# mattduino_v7.net
KiCad netlist of a schematic drawn in EAGLE
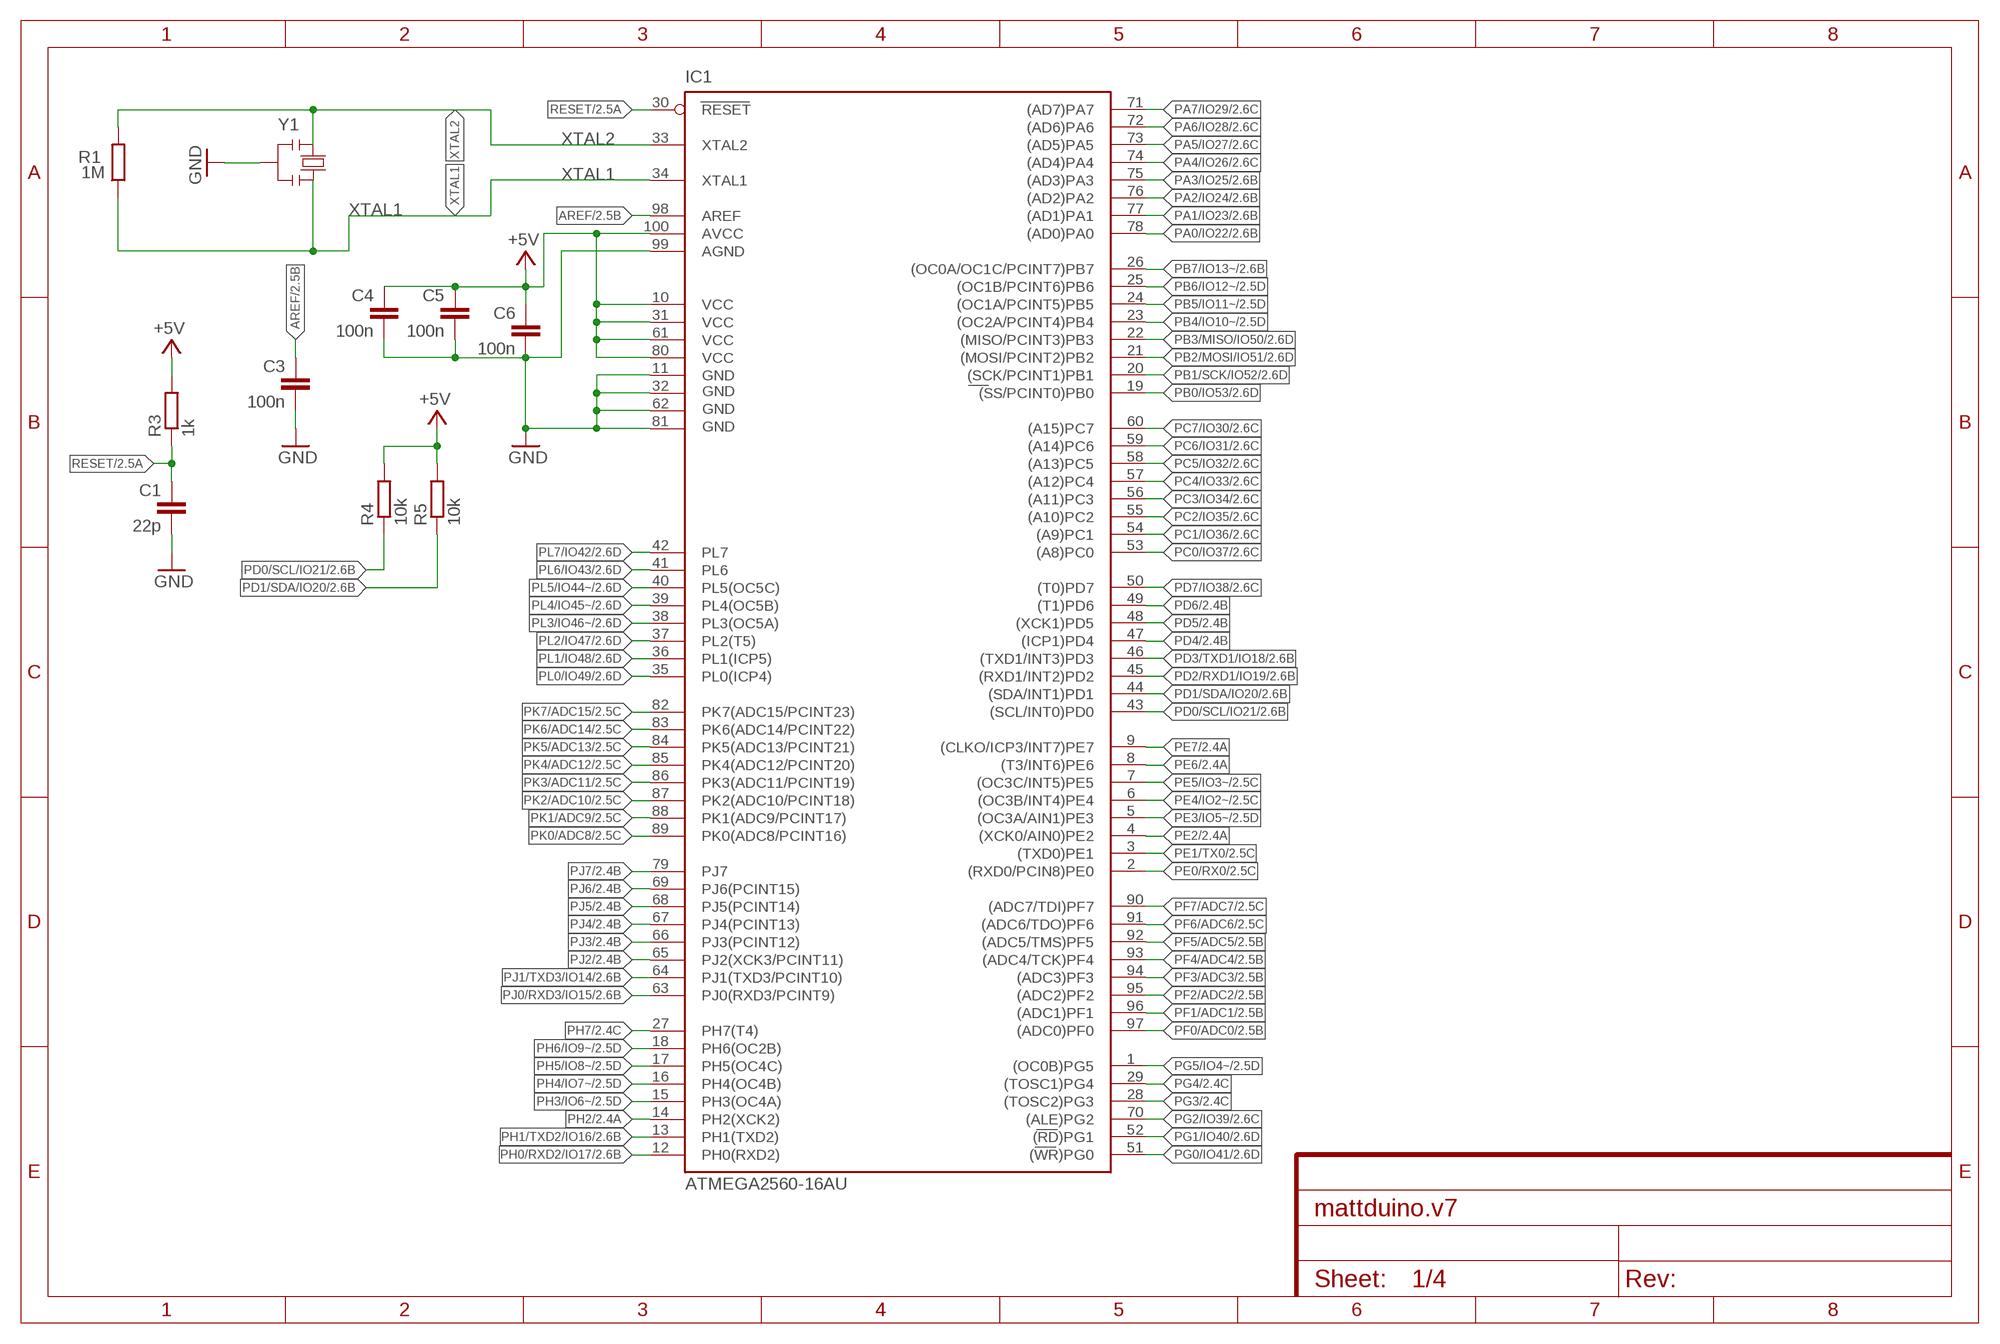
[diagram p0: schematic, sheet 1]
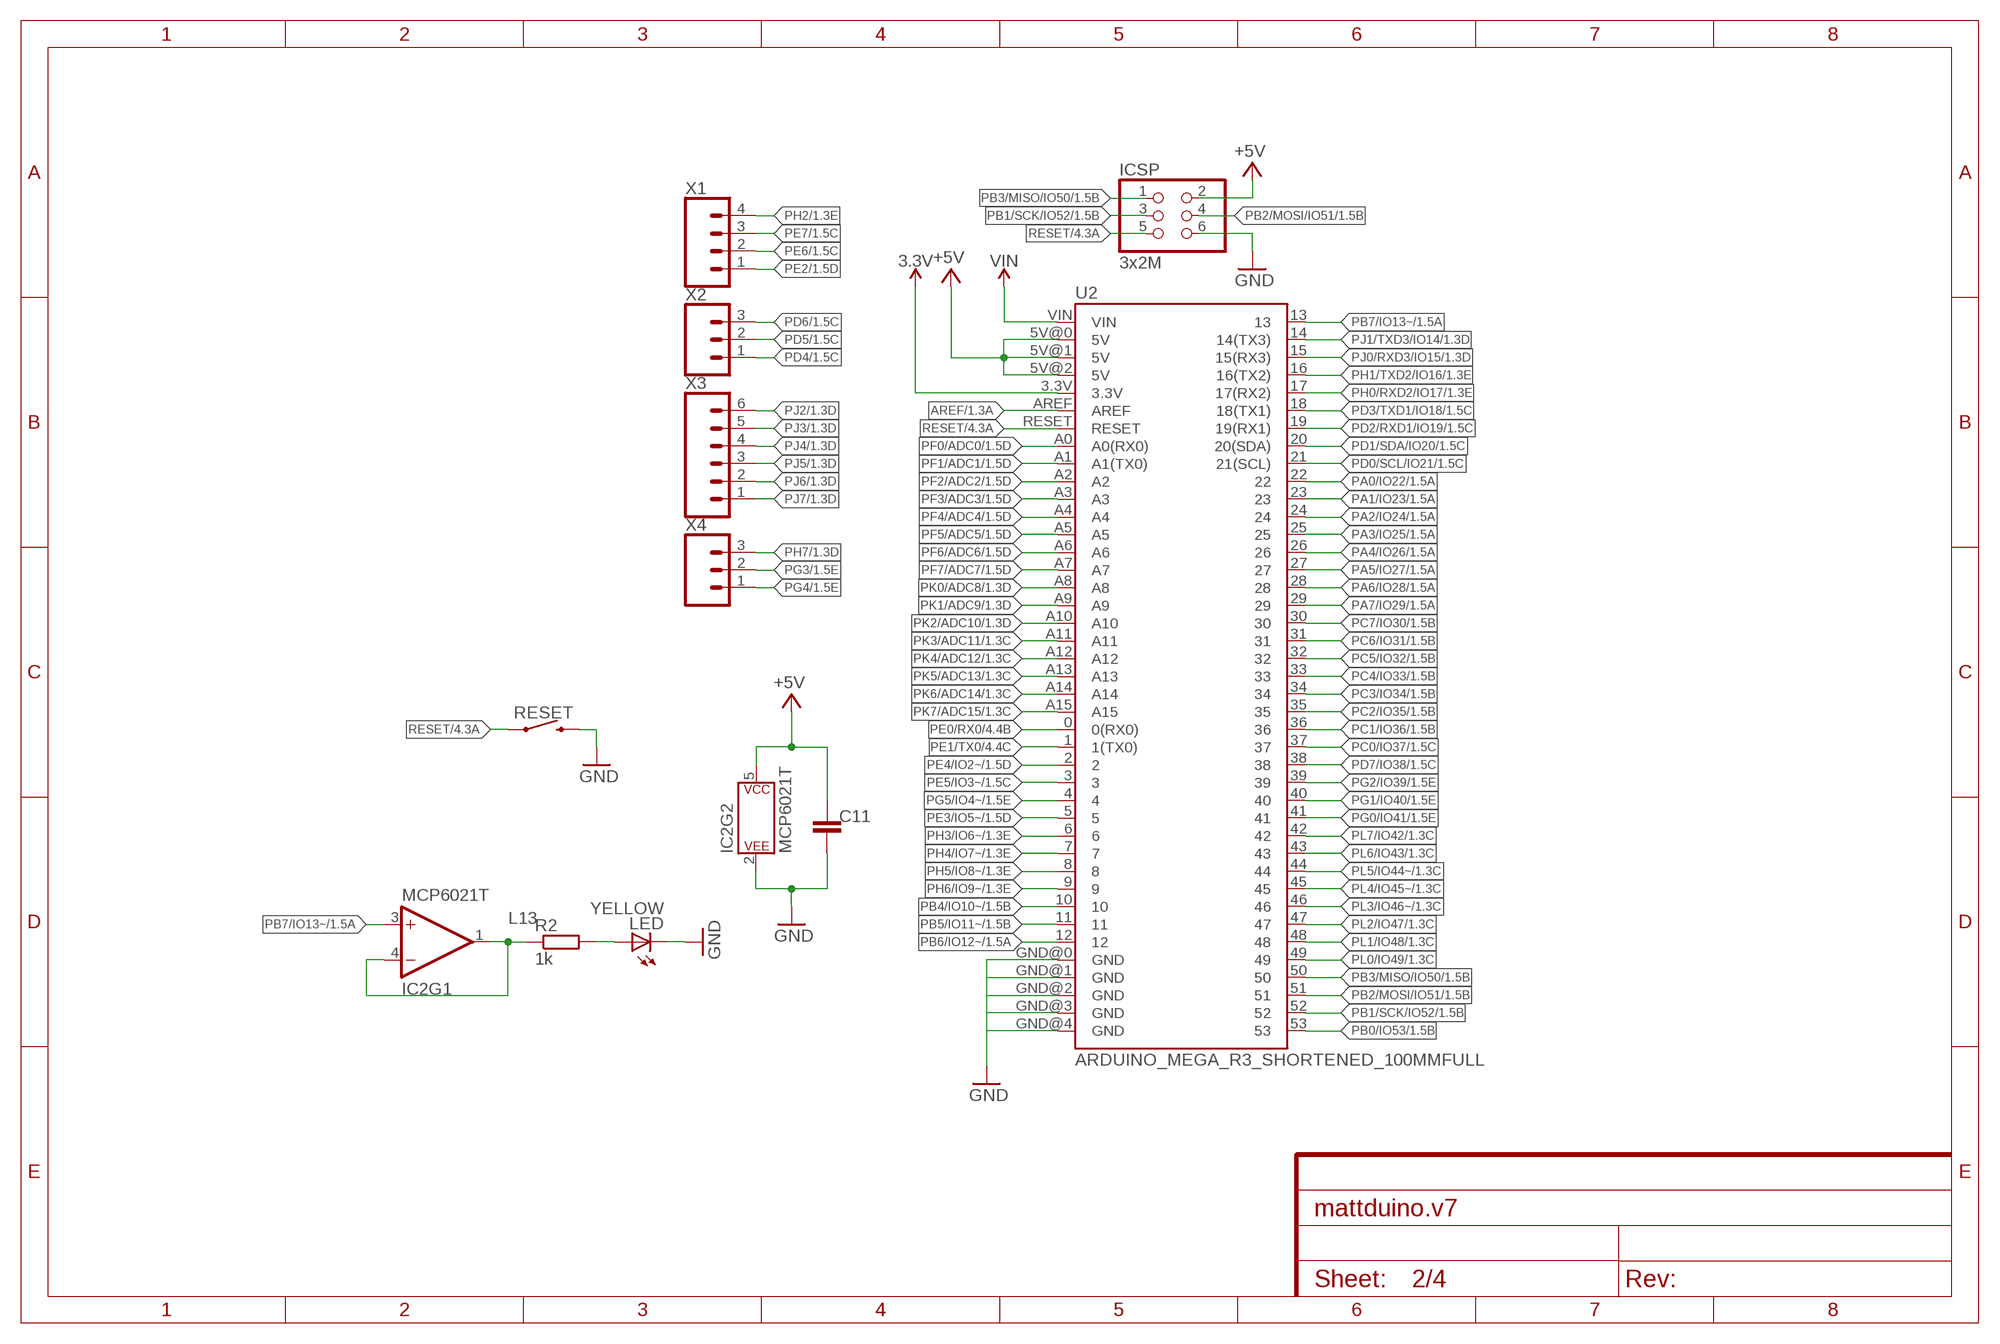
[diagram p1: schematic, sheet 2]
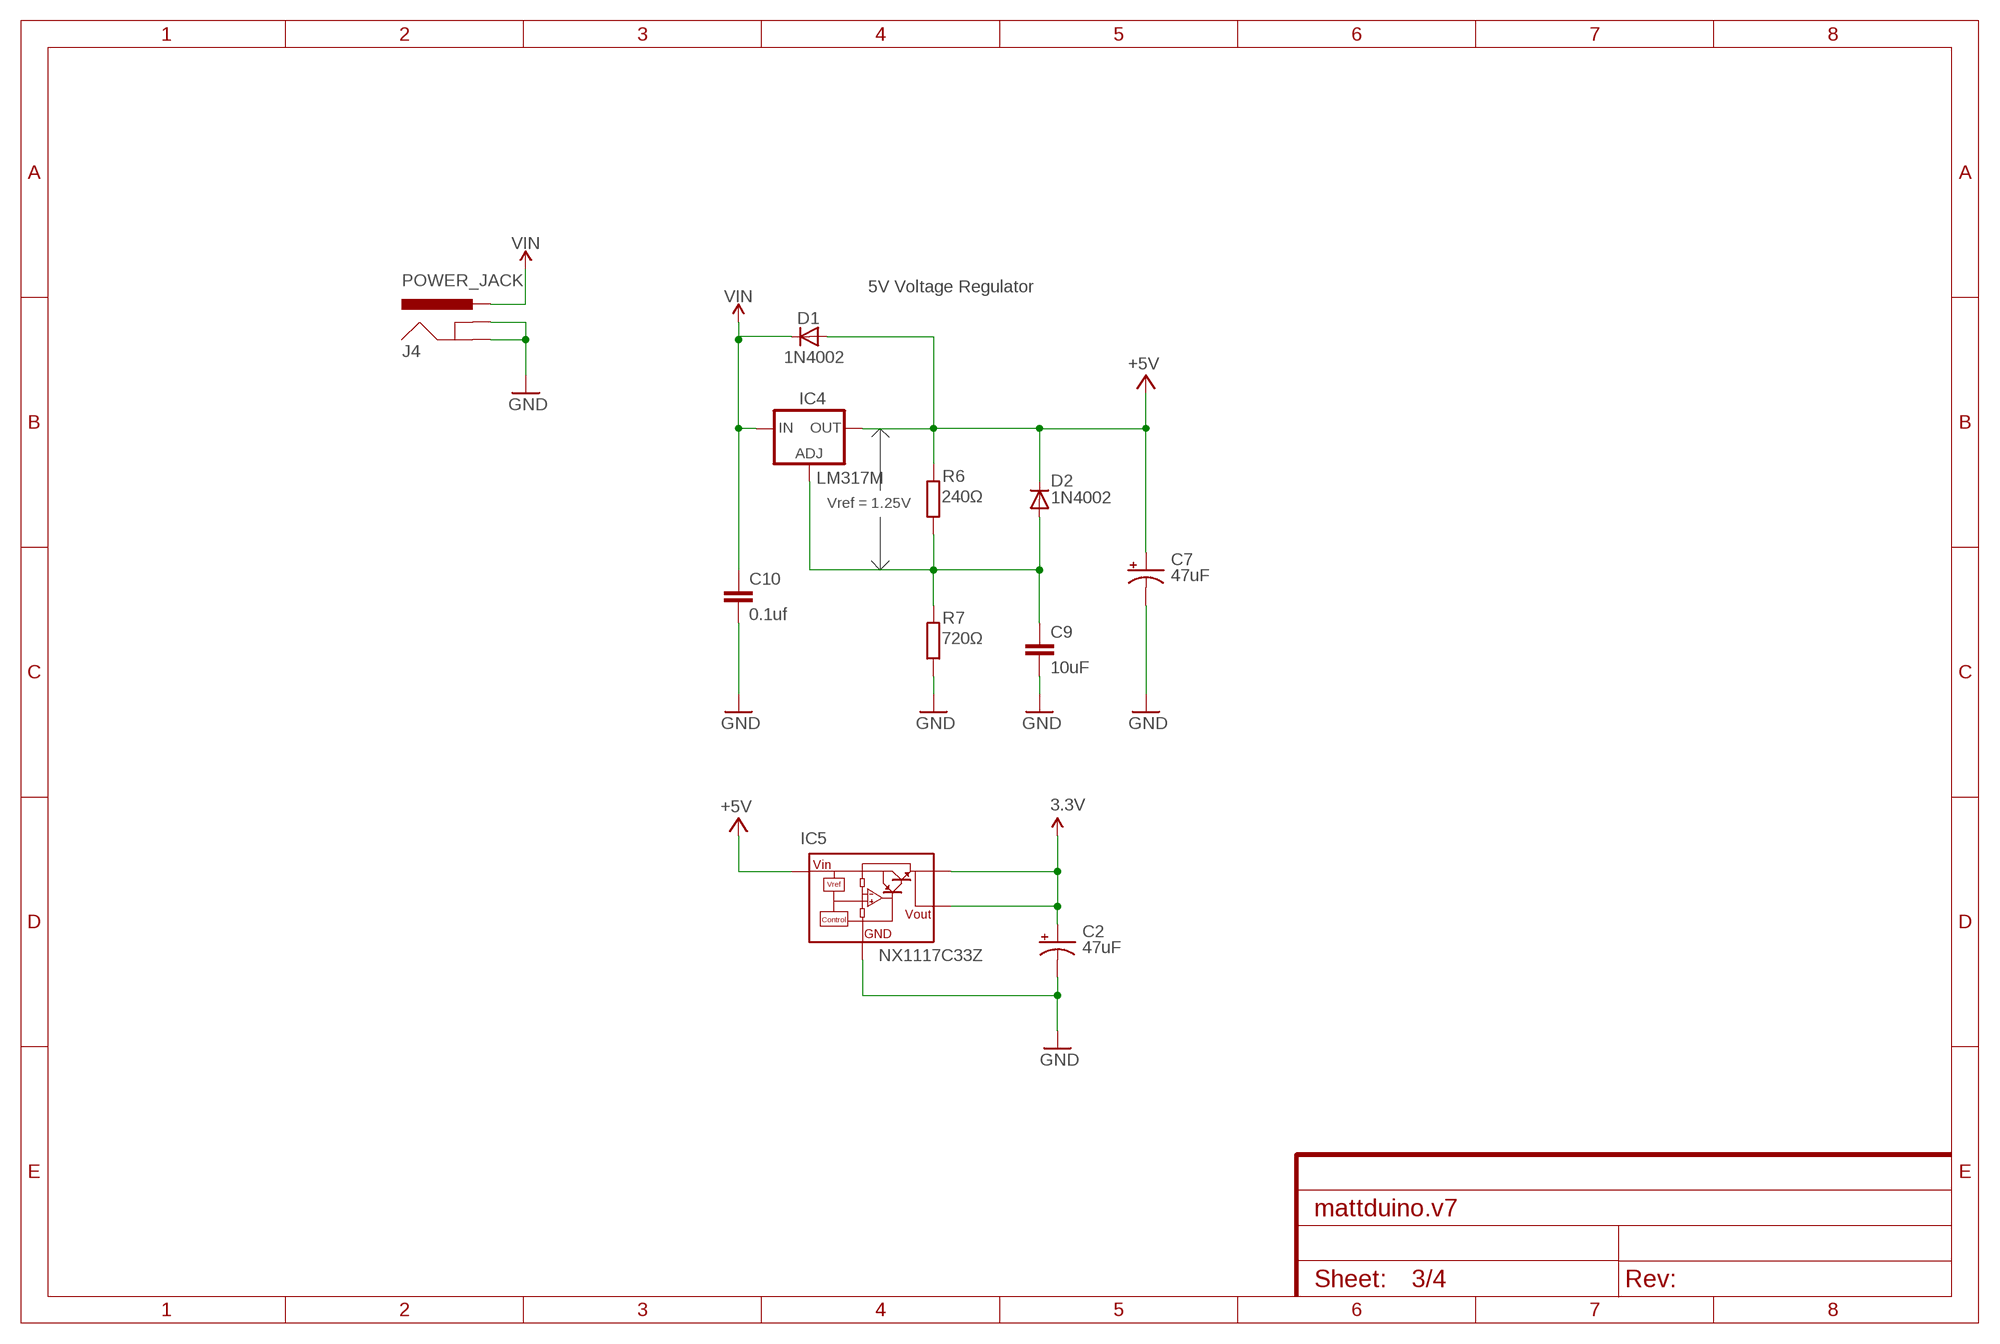
[diagram p2: schematic, sheet 3]
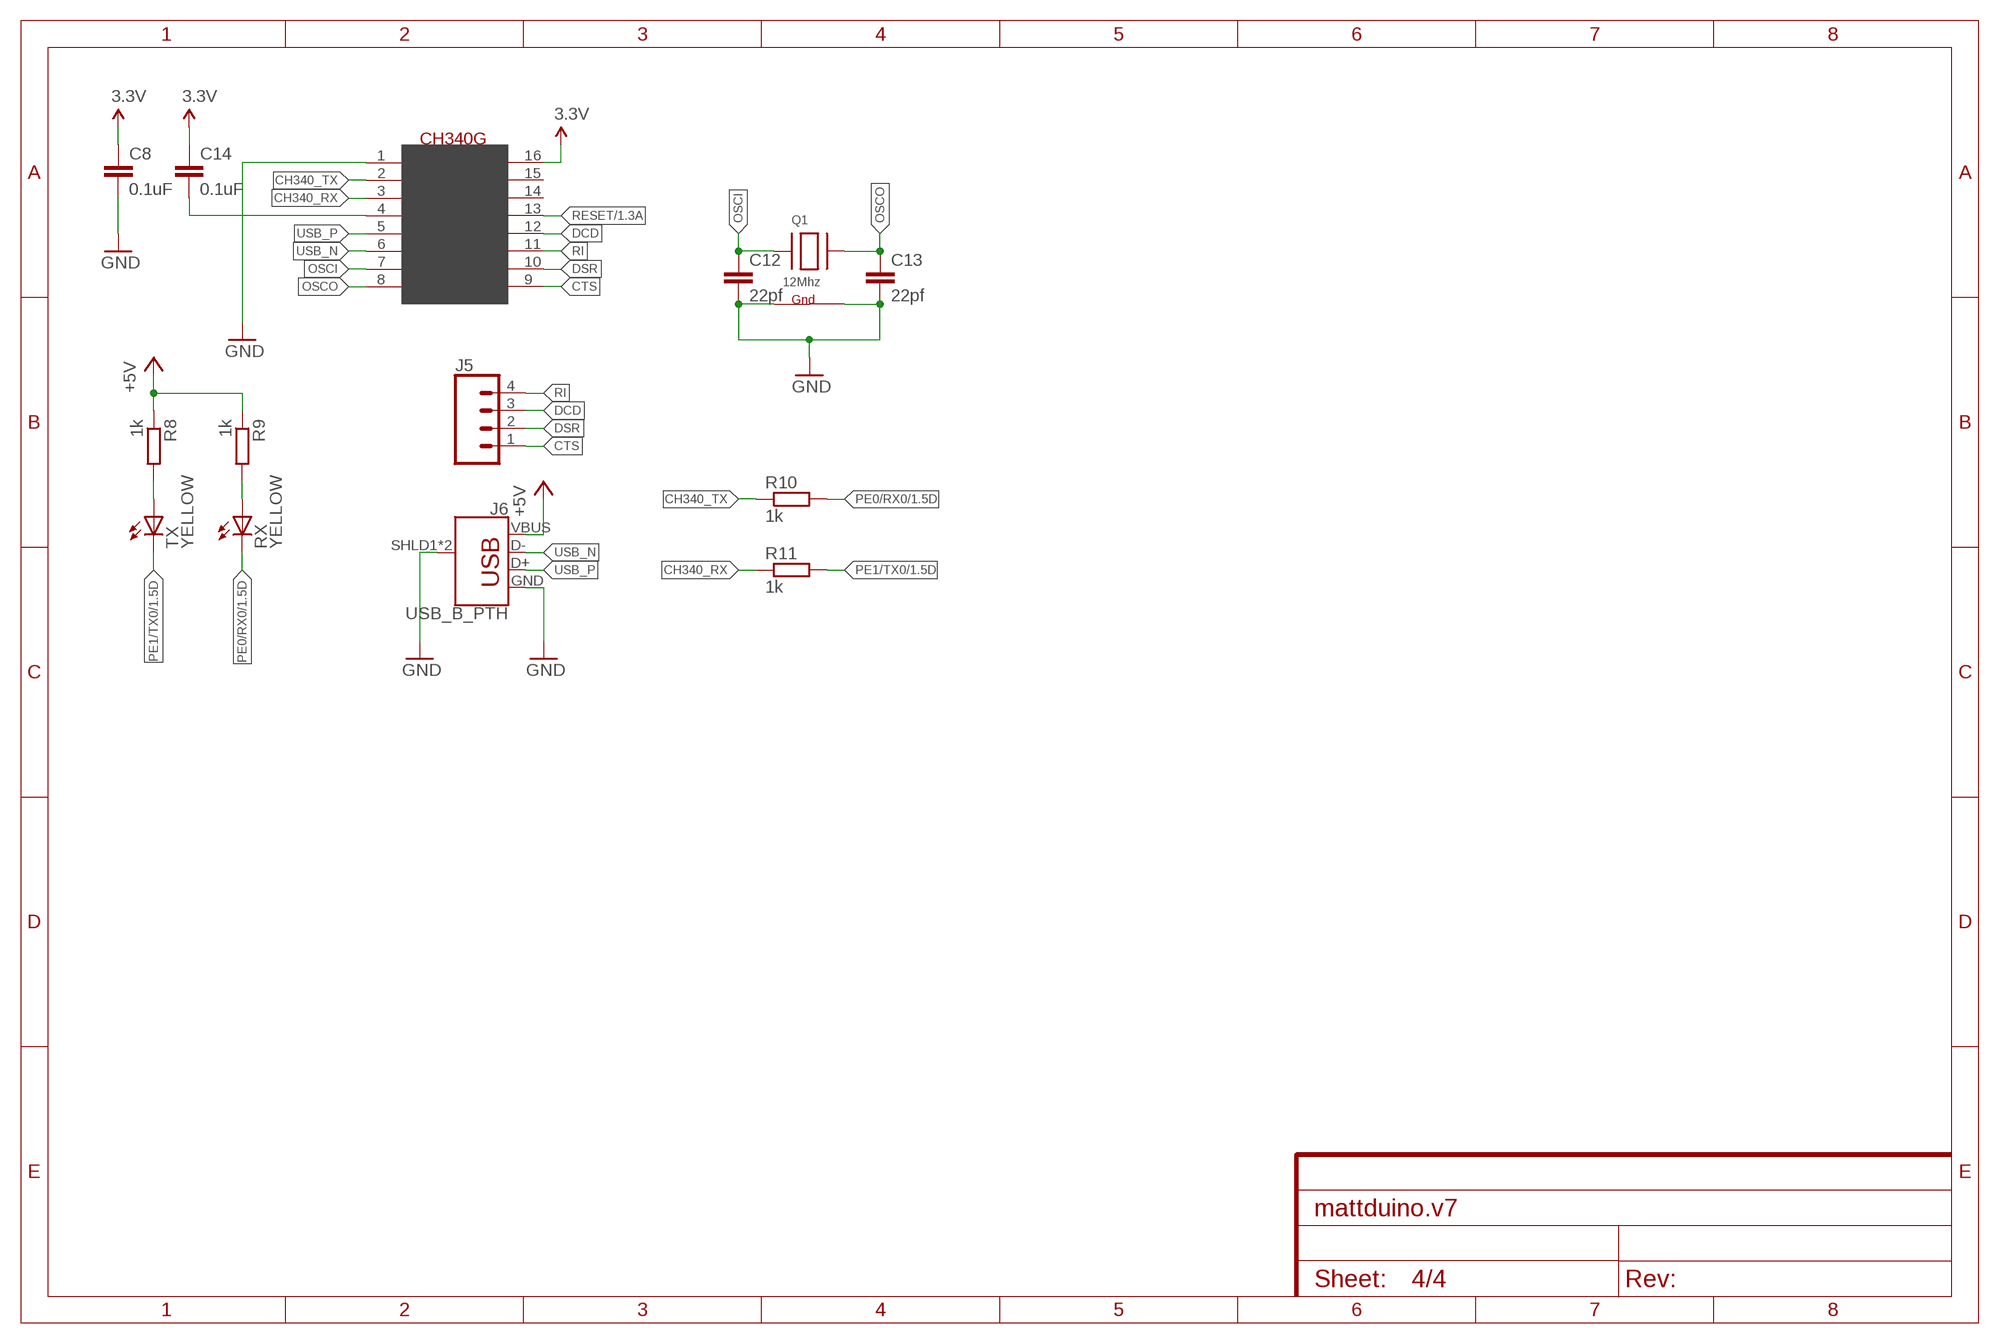
[diagram p3: schematic, sheet 4]

(export (version "E")
  (design (tool "Eeschema 10.0.6"))
  (components
    (comp (ref "C8")
      (value "0.1uF")
      (footprint "eagle-import:C1206")
      (libsource (lib "eagle-import") (part "C-EUC1206"))
    )
    (comp (ref "C12")
      (value "22pf")
      (footprint "eagle-import:C1206")
      (libsource (lib "eagle-import") (part "rcl@1_C-EUC1206"))
    )
    (comp (ref "C13")
      (value "22pf")
      (footprint "eagle-import:C1206")
      (libsource (lib "eagle-import") (part "rcl@1_C-EUC1206"))
    )
    (comp (ref "C14")
      (value "0.1uF")
      (footprint "eagle-import:C1206")
      (libsource (lib "eagle-import") (part "C-EUC1206"))
    )
    (comp (ref "IC3")
      (value "CH340G")
      (footprint "eagle-import:SOIC16")
      (libsource (lib "eagle-import") (part "CH340G"))
    )
    (comp (ref "J5")
      (value "CONN_04")
      (footprint "eagle-import:1X04")
      (libsource (lib "eagle-import") (part "CONN_04"))
    )
    (comp (ref "J6")
      (value "USB_B_PTH")
      (footprint "eagle-import:USB-B-PTH")
      (libsource (lib "eagle-import") (part "USB_B_PTH"))
    )
    (comp (ref "Q1")
      (value "12Mhz")
      (footprint "eagle-import:NX3225")
      (libsource (lib "eagle-import") (part "XTAL-4-3225"))
    )
    (comp (ref "R8")
      (value "1k")
      (footprint "eagle-import:R1206")
      (libsource (lib "eagle-import") (part "R-EU_R1206"))
    )
    (comp (ref "R9")
      (value "1k")
      (footprint "eagle-import:R1206")
      (libsource (lib "eagle-import") (part "R-EU_R1206"))
    )
    (comp (ref "R10")
      (value "1k")
      (footprint "eagle-import:R1206")
      (libsource (lib "eagle-import") (part "R-EU_R1206"))
    )
    (comp (ref "R11")
      (value "1k")
      (footprint "eagle-import:R1206")
      (libsource (lib "eagle-import") (part "R-EU_R1206"))
    )
    (comp (ref "RX")
      (value "YELLOW")
      (footprint "eagle-import:CHIP-LED0805")
      (libsource (lib "eagle-import") (part "LEDCHIP-LED0805"))
    )
    (comp (ref "TX")
      (value "YELLOW")
      (footprint "eagle-import:CHIP-LED0805")
      (libsource (lib "eagle-import") (part "LEDCHIP-LED0805"))
    )
    (comp (ref "C2")
      (value "47uF")
      (footprint "eagle-import:PANASONIC_D")
      (libsource (lib "eagle-import") (part "47UF-POLAR-PANASONIC_D-35V-20%"))
    )
    (comp (ref "C7")
      (value "47uF")
      (footprint "eagle-import:PANASONIC_D")
      (libsource (lib "eagle-import") (part "47UF-POLAR-PANASONIC_D-35V-20%"))
    )
    (comp (ref "C9")
      (value "10uF")
      (footprint "eagle-import:C1206")
      (libsource (lib "eagle-import") (part "C-EUC1206"))
    )
    (comp (ref "C10")
      (value "0.1uf")
      (footprint "eagle-import:C1206")
      (libsource (lib "eagle-import") (part "C-EUC1206"))
    )
    (comp (ref "D1")
      (value "1N4002")
      (footprint "eagle-import:SOD-123")
      (libsource (lib "eagle-import") (part "DIODESOD-123"))
    )
    (comp (ref "D2")
      (value "1N4002")
      (footprint "eagle-import:SOD-123")
      (libsource (lib "eagle-import") (part "DIODESOD-123"))
    )
    (comp (ref "IC4")
      (value "LM317MBSTT3")
      (footprint "eagle-import:SOT223")
      (fields (field (name "PARTNUMBER") "LM317M"))
      (libsource (lib "eagle-import") (part "LM317?MBSTT3"))
    )
    (comp (ref "IC5")
      (value "NX1117C33Z")
      (footprint "eagle-import:SOT223")
      (fields (field (name "TOLERANCE") "1.25%") (field (name "VOLTAGE") "5.0V"))
      (libsource (lib "eagle-import") (part "NX1117CZ33"))
    )
    (comp (ref "J4")
      (value "POWER_JACK")
      (footprint "eagle-import:POWER_JACK_PTH")
      (libsource (lib "eagle-import") (part "POWER_JACK"))
    )
    (comp (ref "R6")
      (value "240Ω")
      (footprint "eagle-import:R1206")
      (libsource (lib "eagle-import") (part "R-EU_R1206"))
    )
    (comp (ref "R7")
      (value "720Ω")
      (footprint "eagle-import:R1206")
      (libsource (lib "eagle-import") (part "R-EU_R1206"))
    )
    (comp (ref "C11")
      (value "100n")
      (footprint "eagle-import:C1206")
      (libsource (lib "eagle-import") (part "C-EUC1206"))
    )
    (comp (ref "IC2")
      (value "MCP6021T")
      (footprint "eagle-import:SOT23-5")
      (libsource (lib "eagle-import") (part "MCP6021T-E/OT"))
    )
    (comp (ref "ICSP")
      (value "3x2M")
      (footprint "eagle-import:2X03")
      (libsource (lib "eagle-import") (part "PINHD-2X3"))
    )
    (comp (ref "LED")
      (value "YELLOW")
      (footprint "eagle-import:CHIP-LED0805")
      (libsource (lib "eagle-import") (part "LEDCHIP-LED0805"))
    )
    (comp (ref "R2")
      (value "1k")
      (footprint "eagle-import:R1206")
      (libsource (lib "eagle-import") (part "R-EU_R1206"))
    )
    (comp (ref "RESET")
      (value "MOMENTARY-SWITCH-SPST-PTH-6.0MM")
      (footprint "eagle-import:TACTILE_SWITCH_PTH_6.0MM")
      (libsource (lib "eagle-import") (part "MOMENTARY-SWITCH-SPST-PTH-6.0MM"))
    )
    (comp (ref "U2")
      (value "ARDUINO_MEGA_R3_SHORTENED_100MMFULL")
      (footprint "eagle-import:ARDUINO_MEGA_SHORTENED_100MM")
      (libsource (lib "eagle-import") (part "ARDUINO_MEGA_R3_SHORTENED_100MMFULL"))
    )
    (comp (ref "X1")
      (value "CONN_04")
      (footprint "eagle-import:1X04")
      (libsource (lib "eagle-import") (part "CONN_04"))
    )
    (comp (ref "X2")
      (value "CONN_03")
      (footprint "eagle-import:1X03")
      (libsource (lib "eagle-import") (part "CONN_03"))
    )
    (comp (ref "X3")
      (value "CONN_06SILK_FEMALE_PTH")
      (footprint "eagle-import:1X06")
      (libsource (lib "eagle-import") (part "CONN_06SILK_FEMALE_PTH"))
    )
    (comp (ref "X4")
      (value "CONN_03")
      (footprint "eagle-import:1X03")
      (libsource (lib "eagle-import") (part "CONN_03"))
    )
    (comp (ref "C1")
      (value "22p")
      (footprint "eagle-import:C1206")
      (libsource (lib "eagle-import") (part "C-EUC1206"))
    )
    (comp (ref "C3")
      (value "100n")
      (footprint "eagle-import:C1206")
      (libsource (lib "eagle-import") (part "C-EUC1206"))
    )
    (comp (ref "C4")
      (value "100n")
      (footprint "eagle-import:C1206")
      (libsource (lib "eagle-import") (part "C-EUC1206"))
    )
    (comp (ref "C5")
      (value "100n")
      (footprint "eagle-import:C1206")
      (libsource (lib "eagle-import") (part "C-EUC1206"))
    )
    (comp (ref "C6")
      (value "100n")
      (footprint "eagle-import:C1206")
      (libsource (lib "eagle-import") (part "C-EUC1206"))
    )
    (comp (ref "IC1")
      (value "ATMEGA2560-16AU")
      (footprint "eagle-import:TQFP100")
      (libsource (lib "eagle-import") (part "ATMEGA2560AU2560-16"))
    )
    (comp (ref "R1")
      (value "1M")
      (footprint "eagle-import:R1206")
      (libsource (lib "eagle-import") (part "R-EU_R1206"))
    )
    (comp (ref "R3")
      (value "1k")
      (footprint "eagle-import:R1206")
      (libsource (lib "eagle-import") (part "R-EU_R1206"))
    )
    (comp (ref "R4")
      (value "10k")
      (footprint "eagle-import:R1206")
      (libsource (lib "eagle-import") (part "R-EU_R1206"))
    )
    (comp (ref "R5")
      (value "10k")
      (footprint "eagle-import:R1206")
      (libsource (lib "eagle-import") (part "R-EU_R1206"))
    )
    (comp (ref "Y1")
      (value "CSTCE16M0V53-R0 16MHZ")
      (footprint "eagle-import:RESONATOR")
      (libsource (lib "eagle-import") (part "RESONATORMU"))
    )
  )
  (nets
    (net (code "1") (name "+5V") (class "Default")
      (node (ref "C11") (pin "2") (pinfunction "2_2") (pintype "passive"))
      (node (ref "C4") (pin "1") (pinfunction "1_1") (pintype "passive"))
      (node (ref "C5") (pin "1") (pinfunction "1_1") (pintype "passive"))
      (node (ref "C6") (pin "1") (pinfunction "1_1") (pintype "passive"))
      (node (ref "C7") (pin "+") (pinfunction "+_+") (pintype "passive"))
      (node (ref "D1") (pin "A") (pinfunction "A_A") (pintype "passive"))
      (node (ref "D2") (pin "C") (pinfunction "C_C") (pintype "passive"))
      (node (ref "IC1") (pin "10") (pinfunction "VCC_10") (pintype "power_in"))
      (node (ref "IC1") (pin "100") (pinfunction "AVCC_100") (pintype "power_in"))
      (node (ref "IC1") (pin "31") (pinfunction "VCC1_31") (pintype "power_in"))
      (node (ref "IC1") (pin "61") (pinfunction "VCC2_61") (pintype "power_in"))
      (node (ref "IC1") (pin "80") (pinfunction "VCC3_80") (pintype "power_in"))
      (node (ref "IC2") (pin "5") (pinfunction "P$V+_5") (pintype "bidirectional"))
      (node (ref "IC4") (pin "4") (pinfunction "OUT_4") (pintype "passive"))
      (node (ref "IC5") (pin "3") (pinfunction "VIN_3") (pintype "input"))
      (node (ref "ICSP") (pin "2") (pinfunction "2_2") (pintype "passive"))
      (node (ref "J6") (pin "VBUS") (pinfunction "VBUS_VBUS") (pintype "power_in"))
      (node (ref "R3") (pin "2") (pinfunction "2_2") (pintype "passive"))
      (node (ref "R4") (pin "2") (pinfunction "2_2") (pintype "passive"))
      (node (ref "R5") (pin "2") (pinfunction "2_2") (pintype "passive"))
      (node (ref "R6") (pin "2") (pinfunction "2_2") (pintype "passive"))
      (node (ref "R8") (pin "1") (pinfunction "1_1") (pintype "passive"))
      (node (ref "R9") (pin "1") (pinfunction "1_1") (pintype "passive"))
      (node (ref "U2") (pin "5V@0") (pinfunction "5V_5V@0") (pintype "bidirectional"))
      (node (ref "U2") (pin "5V@1") (pinfunction "5V_5V@1") (pintype "bidirectional"))
      (node (ref "U2") (pin "5V@2") (pinfunction "5V_5V@2") (pintype "bidirectional"))
    )
    (net (code "2") (name "3.3V") (class "Default")
      (node (ref "C14") (pin "1") (pinfunction "1_1") (pintype "passive"))
      (node (ref "C2") (pin "+") (pinfunction "+_+") (pintype "passive"))
      (node (ref "C8") (pin "1") (pinfunction "1_1") (pintype "passive"))
      (node (ref "IC3") (pin "16") (pinfunction "VCC_16") (pintype "bidirectional"))
      (node (ref "IC5") (pin "2") (pinfunction "VOUT1_2") (pintype "output"))
      (node (ref "IC5") (pin "4") (pinfunction "VOUT_4") (pintype "output"))
      (node (ref "U2") (pin "3.3V") (pinfunction "3.3V_3.3V") (pintype "bidirectional"))
    )
    (net (code "3") (name "AREF") (class "Default")
      (node (ref "C3") (pin "1") (pinfunction "1_1") (pintype "passive"))
      (node (ref "IC1") (pin "98") (pinfunction "AREF_98") (pintype "bidirectional"))
      (node (ref "U2") (pin "AREF") (pinfunction "AREF_AREF") (pintype "bidirectional"))
    )
    (net (code "4") (name "CH340_RX") (class "Default")
      (node (ref "IC3") (pin "3") (pinfunction "RX_3") (pintype "bidirectional"))
      (node (ref "R11") (pin "1") (pinfunction "1_1") (pintype "passive"))
    )
    (net (code "5") (name "CH340_TX") (class "Default")
      (node (ref "IC3") (pin "2") (pinfunction "TX_2") (pintype "bidirectional"))
      (node (ref "R10") (pin "1") (pinfunction "1_1") (pintype "passive"))
    )
    (net (code "6") (name "CTS") (class "Default")
      (node (ref "IC3") (pin "9") (pinfunction "CTS_9") (pintype "bidirectional"))
      (node (ref "J5") (pin "1") (pinfunction "1_1") (pintype "passive"))
    )
    (net (code "7") (name "DCD") (class "Default")
      (node (ref "IC3") (pin "12") (pinfunction "DCD_12") (pintype "bidirectional"))
      (node (ref "J5") (pin "3") (pinfunction "3_3") (pintype "passive"))
    )
    (net (code "8") (name "DSR") (class "Default")
      (node (ref "IC3") (pin "10") (pinfunction "DSR_10") (pintype "bidirectional"))
      (node (ref "J5") (pin "2") (pinfunction "2_2") (pintype "passive"))
    )
    (net (code "9") (name "GND") (class "Default")
      (node (ref "C1") (pin "2") (pinfunction "2_2") (pintype "passive"))
      (node (ref "C10") (pin "2") (pinfunction "2_2") (pintype "passive"))
      (node (ref "C11") (pin "1") (pinfunction "1_1") (pintype "passive"))
      (node (ref "C12") (pin "2") (pinfunction "2_2") (pintype "passive"))
      (node (ref "C13") (pin "2") (pinfunction "2_2") (pintype "passive"))
      (node (ref "C2") (pin "-") (pinfunction "-_-") (pintype "passive"))
      (node (ref "C3") (pin "2") (pinfunction "2_2") (pintype "passive"))
      (node (ref "C4") (pin "2") (pinfunction "2_2") (pintype "passive"))
      (node (ref "C5") (pin "2") (pinfunction "2_2") (pintype "passive"))
      (node (ref "C6") (pin "2") (pinfunction "2_2") (pintype "passive"))
      (node (ref "C7") (pin "-") (pinfunction "-_-") (pintype "passive"))
      (node (ref "C8") (pin "2") (pinfunction "2_2") (pintype "passive"))
      (node (ref "C9") (pin "2") (pinfunction "2_2") (pintype "passive"))
      (node (ref "IC1") (pin "11") (pinfunction "GND_11") (pintype "power_in"))
      (node (ref "IC1") (pin "32") (pinfunction "GND1_32") (pintype "power_in"))
      (node (ref "IC1") (pin "62") (pinfunction "GND2_62") (pintype "power_in"))
      (node (ref "IC1") (pin "81") (pinfunction "GND3_81") (pintype "power_in"))
      (node (ref "IC1") (pin "99") (pinfunction "AGND_99") (pintype "power_in"))
      (node (ref "IC2") (pin "2") (pinfunction "P$V-_2") (pintype "bidirectional"))
      (node (ref "IC3") (pin "1") (pinfunction "GND_1") (pintype "bidirectional"))
      (node (ref "IC5") (pin "1") (pinfunction "GND_1") (pintype "passive"))
      (node (ref "ICSP") (pin "6") (pinfunction "6_6") (pintype "passive"))
      (node (ref "J4") (pin "GND") (pinfunction "GND_GND") (pintype "bidirectional"))
      (node (ref "J4") (pin "GNDBREAK") (pinfunction "GNDBREAK_GNDBREAK") (pintype "bidirectional"))
      (node (ref "J6") (pin "GND") (pinfunction "GND_GND") (pintype "power_in"))
      (node (ref "J6") (pin "SHLD1") (pinfunction "SHIELD_SHLD1") (pintype "bidirectional"))
      (node (ref "J6") (pin "SHLD2") (pinfunction "SHIELD_SHLD2") (pintype "bidirectional"))
      (node (ref "LED") (pin "C") (pinfunction "C_C") (pintype "passive"))
      (node (ref "Q1") (pin "2") (pinfunction "G2_2") (pintype "power_in"))
      (node (ref "Q1") (pin "4") (pinfunction "G1_4") (pintype "power_in"))
      (node (ref "R7") (pin "1") (pinfunction "1_1") (pintype "passive"))
      (node (ref "RESET") (pin "3") (pinfunction "2_3") (pintype "passive"))
      (node (ref "U2") (pin "GND@0") (pinfunction "GND_GND@0") (pintype "bidirectional"))
      (node (ref "U2") (pin "GND@1") (pinfunction "GND_GND@1") (pintype "bidirectional"))
      (node (ref "U2") (pin "GND@2") (pinfunction "GND_GND@2") (pintype "bidirectional"))
      (node (ref "U2") (pin "GND@3") (pinfunction "GND_GND@3") (pintype "bidirectional"))
      (node (ref "U2") (pin "GND@4") (pinfunction "GND_GND@4") (pintype "bidirectional"))
      (node (ref "Y1") (pin "2") (pinfunction "2_2") (pintype "passive"))
    )
    (net (code "10") (name "L13") (class "Default")
      (node (ref "IC2") (pin "1") (pinfunction "OUT_1") (pintype "output"))
      (node (ref "IC2") (pin "4") (pinfunction "-IN_4") (pintype "input"))
      (node (ref "R2") (pin "1") (pinfunction "1_1") (pintype "passive"))
    )
    (net (code "11") (name "Net-(IC3-V3)") (class "Default")
      (node (ref "C14") (pin "2") (pinfunction "2_2") (pintype "passive"))
      (node (ref "IC3") (pin "4") (pinfunction "V3_4") (pintype "bidirectional"))
    )
    (net (code "12") (name "Net-(IC4-ADJ)") (class "Default")
      (node (ref "C9") (pin "1") (pinfunction "1_1") (pintype "passive"))
      (node (ref "D2") (pin "A") (pinfunction "A_A") (pintype "passive"))
      (node (ref "IC4") (pin "1") (pinfunction "ADJ_1") (pintype "input"))
      (node (ref "R6") (pin "1") (pinfunction "1_1") (pintype "passive"))
      (node (ref "R7") (pin "2") (pinfunction "2_2") (pintype "passive"))
    )
    (net (code "13") (name "Net-(LED-PadA)") (class "Default")
      (node (ref "LED") (pin "A") (pinfunction "A_A") (pintype "passive"))
      (node (ref "R2") (pin "2") (pinfunction "2_2") (pintype "passive"))
    )
    (net (code "14") (name "Net-(R8-Pad2)") (class "Default")
      (node (ref "R8") (pin "2") (pinfunction "2_2") (pintype "passive"))
      (node (ref "TX") (pin "A") (pinfunction "A_A") (pintype "passive"))
    )
    (net (code "15") (name "Net-(R9-Pad2)") (class "Default")
      (node (ref "R9") (pin "2") (pinfunction "2_2") (pintype "passive"))
      (node (ref "RX") (pin "A") (pinfunction "A_A") (pintype "passive"))
    )
    (net (code "16") (name "OSCI") (class "Default")
      (node (ref "C12") (pin "1") (pinfunction "1_1") (pintype "passive"))
      (node (ref "IC3") (pin "7") (pinfunction "XI_7") (pintype "bidirectional"))
      (node (ref "Q1") (pin "1") (pinfunction "X1_1") (pintype "bidirectional"))
    )
    (net (code "17") (name "OSCO") (class "Default")
      (node (ref "C13") (pin "1") (pinfunction "1_1") (pintype "passive"))
      (node (ref "IC3") (pin "8") (pinfunction "XO_8") (pintype "bidirectional"))
      (node (ref "Q1") (pin "3") (pinfunction "X2_3") (pintype "bidirectional"))
    )
    (net (code "18") (name "PA0{slash}IO22") (class "Default")
      (node (ref "IC1") (pin "78") (pinfunction "(AD0)PA0_78") (pintype "bidirectional"))
      (node (ref "U2") (pin "22") (pinfunction "22_22") (pintype "bidirectional"))
    )
    (net (code "19") (name "PA1{slash}IO23") (class "Default")
      (node (ref "IC1") (pin "77") (pinfunction "(AD1)PA1_77") (pintype "bidirectional"))
      (node (ref "U2") (pin "23") (pinfunction "23_23") (pintype "bidirectional"))
    )
    (net (code "20") (name "PA2{slash}IO24") (class "Default")
      (node (ref "IC1") (pin "76") (pinfunction "(AD2)PA2_76") (pintype "bidirectional"))
      (node (ref "U2") (pin "24") (pinfunction "24_24") (pintype "bidirectional"))
    )
    (net (code "21") (name "PA3{slash}IO25") (class "Default")
      (node (ref "IC1") (pin "75") (pinfunction "(AD3)PA3_75") (pintype "bidirectional"))
      (node (ref "U2") (pin "25") (pinfunction "25_25") (pintype "bidirectional"))
    )
    (net (code "22") (name "PA4{slash}IO26") (class "Default")
      (node (ref "IC1") (pin "74") (pinfunction "(AD4)PA4_74") (pintype "bidirectional"))
      (node (ref "U2") (pin "26") (pinfunction "26_26") (pintype "bidirectional"))
    )
    (net (code "23") (name "PA5{slash}IO27") (class "Default")
      (node (ref "IC1") (pin "73") (pinfunction "(AD5)PA5_73") (pintype "bidirectional"))
      (node (ref "U2") (pin "27") (pinfunction "27_27") (pintype "bidirectional"))
    )
    (net (code "24") (name "PA6{slash}IO28") (class "Default")
      (node (ref "IC1") (pin "72") (pinfunction "(AD6)PA6_72") (pintype "bidirectional"))
      (node (ref "U2") (pin "28") (pinfunction "28_28") (pintype "bidirectional"))
    )
    (net (code "25") (name "PA7{slash}IO29") (class "Default")
      (node (ref "IC1") (pin "71") (pinfunction "(AD7)PA7_71") (pintype "bidirectional"))
      (node (ref "U2") (pin "29") (pinfunction "29_29") (pintype "bidirectional"))
    )
    (net (code "26") (name "PB0{slash}IO53") (class "Default")
      (node (ref "IC1") (pin "19") (pinfunction "(SS/PCINT0)PB0_19") (pintype "bidirectional"))
      (node (ref "U2") (pin "53") (pinfunction "53_53") (pintype "bidirectional"))
    )
    (net (code "27") (name "PB1{slash}SCK{slash}IO52") (class "Default")
      (node (ref "IC1") (pin "20") (pinfunction "(SCK/PCINT1)PB1_20") (pintype "bidirectional"))
      (node (ref "ICSP") (pin "3") (pinfunction "3_3") (pintype "passive"))
      (node (ref "U2") (pin "52") (pinfunction "52_52") (pintype "bidirectional"))
    )
    (net (code "28") (name "PB2{slash}MOSI{slash}IO51") (class "Default")
      (node (ref "IC1") (pin "21") (pinfunction "(MOSI/PCINT2)PB2_21") (pintype "bidirectional"))
      (node (ref "ICSP") (pin "4") (pinfunction "4_4") (pintype "passive"))
      (node (ref "U2") (pin "51") (pinfunction "51_51") (pintype "bidirectional"))
    )
    (net (code "29") (name "PB3{slash}MISO{slash}IO50") (class "Default")
      (node (ref "IC1") (pin "22") (pinfunction "(MISO/PCINT3)PB3_22") (pintype "bidirectional"))
      (node (ref "ICSP") (pin "1") (pinfunction "1_1") (pintype "passive"))
      (node (ref "U2") (pin "50") (pinfunction "50_50") (pintype "bidirectional"))
    )
    (net (code "30") (name "PB4{slash}IO10~{}") (class "Default")
      (node (ref "IC1") (pin "23") (pinfunction "(OC2A/PCINT4)PB4_23") (pintype "bidirectional"))
      (node (ref "U2") (pin "10") (pinfunction "10_10") (pintype "bidirectional"))
    )
    (net (code "31") (name "PB5{slash}IO11~{}") (class "Default")
      (node (ref "IC1") (pin "24") (pinfunction "(OC1A/PCINT5)PB5_24") (pintype "bidirectional"))
      (node (ref "U2") (pin "11") (pinfunction "11_11") (pintype "bidirectional"))
    )
    (net (code "32") (name "PB6{slash}IO12~{}") (class "Default")
      (node (ref "IC1") (pin "25") (pinfunction "(OC1B/PCINT6)PB6_25") (pintype "bidirectional"))
      (node (ref "U2") (pin "12") (pinfunction "12_12") (pintype "bidirectional"))
    )
    (net (code "33") (name "PB7{slash}IO13~{}") (class "Default")
      (node (ref "IC1") (pin "26") (pinfunction "(OC0A/OC1C/PCINT7)PB7_26") (pintype "bidirectional"))
      (node (ref "IC2") (pin "3") (pinfunction "+IN_3") (pintype "input"))
      (node (ref "U2") (pin "13") (pinfunction "13_13") (pintype "bidirectional"))
    )
    (net (code "34") (name "PC0{slash}IO37") (class "Default")
      (node (ref "IC1") (pin "53") (pinfunction "(A8)PC0_53") (pintype "bidirectional"))
      (node (ref "U2") (pin "37") (pinfunction "37_37") (pintype "bidirectional"))
    )
    (net (code "35") (name "PC1{slash}IO36") (class "Default")
      (node (ref "IC1") (pin "54") (pinfunction "(A9)PC1_54") (pintype "bidirectional"))
      (node (ref "U2") (pin "36") (pinfunction "36_36") (pintype "bidirectional"))
    )
    (net (code "36") (name "PC2{slash}IO35") (class "Default")
      (node (ref "IC1") (pin "55") (pinfunction "(A10)PC2_55") (pintype "bidirectional"))
      (node (ref "U2") (pin "35") (pinfunction "35_35") (pintype "bidirectional"))
    )
    (net (code "37") (name "PC3{slash}IO34") (class "Default")
      (node (ref "IC1") (pin "56") (pinfunction "(A11)PC3_56") (pintype "bidirectional"))
      (node (ref "U2") (pin "34") (pinfunction "34_34") (pintype "bidirectional"))
    )
    (net (code "38") (name "PC4{slash}IO33") (class "Default")
      (node (ref "IC1") (pin "57") (pinfunction "(A12)PC4_57") (pintype "bidirectional"))
      (node (ref "U2") (pin "33") (pinfunction "33_33") (pintype "bidirectional"))
    )
    (net (code "39") (name "PC5{slash}IO32") (class "Default")
      (node (ref "IC1") (pin "58") (pinfunction "(A13)PC5_58") (pintype "bidirectional"))
      (node (ref "U2") (pin "32") (pinfunction "32_32") (pintype "bidirectional"))
    )
    (net (code "40") (name "PC6{slash}IO31") (class "Default")
      (node (ref "IC1") (pin "59") (pinfunction "(A14)PC6_59") (pintype "bidirectional"))
      (node (ref "U2") (pin "31") (pinfunction "31_31") (pintype "bidirectional"))
    )
    (net (code "41") (name "PC7{slash}IO30") (class "Default")
      (node (ref "IC1") (pin "60") (pinfunction "(A15)PC7_60") (pintype "bidirectional"))
      (node (ref "U2") (pin "30") (pinfunction "30_30") (pintype "bidirectional"))
    )
    (net (code "42") (name "PD0{slash}SCL{slash}IO21") (class "Default")
      (node (ref "IC1") (pin "43") (pinfunction "(SCL/INT0)PD0_43") (pintype "bidirectional"))
      (node (ref "R4") (pin "1") (pinfunction "1_1") (pintype "passive"))
      (node (ref "U2") (pin "21") (pinfunction "21(SCL)_21") (pintype "bidirectional"))
    )
    (net (code "43") (name "PD1{slash}SDA{slash}IO20") (class "Default")
      (node (ref "IC1") (pin "44") (pinfunction "(SDA/INT1)PD1_44") (pintype "bidirectional"))
      (node (ref "R5") (pin "1") (pinfunction "1_1") (pintype "passive"))
      (node (ref "U2") (pin "20") (pinfunction "20(SDA)_20") (pintype "bidirectional"))
    )
    (net (code "44") (name "PD2{slash}RXD1{slash}IO19") (class "Default")
      (node (ref "IC1") (pin "45") (pinfunction "(RXD1/INT2)PD2_45") (pintype "bidirectional"))
      (node (ref "U2") (pin "19") (pinfunction "19(RX1)_19") (pintype "bidirectional"))
    )
    (net (code "45") (name "PD3{slash}TXD1{slash}IO18") (class "Default")
      (node (ref "IC1") (pin "46") (pinfunction "(TXD1/INT3)PD3_46") (pintype "bidirectional"))
      (node (ref "U2") (pin "18") (pinfunction "18(TX1)_18") (pintype "bidirectional"))
    )
    (net (code "46") (name "PD4") (class "Default")
      (node (ref "IC1") (pin "47") (pinfunction "(ICP1)PD4_47") (pintype "bidirectional"))
      (node (ref "X2") (pin "1") (pinfunction "1_1") (pintype "passive"))
    )
    (net (code "47") (name "PD5") (class "Default")
      (node (ref "IC1") (pin "48") (pinfunction "(XCK1)PD5_48") (pintype "bidirectional"))
      (node (ref "X2") (pin "2") (pinfunction "2_2") (pintype "passive"))
    )
    (net (code "48") (name "PD6") (class "Default")
      (node (ref "IC1") (pin "49") (pinfunction "(T1)PD6_49") (pintype "bidirectional"))
      (node (ref "X2") (pin "3") (pinfunction "3_3") (pintype "passive"))
    )
    (net (code "49") (name "PD7{slash}IO38") (class "Default")
      (node (ref "IC1") (pin "50") (pinfunction "(T0)PD7_50") (pintype "bidirectional"))
      (node (ref "U2") (pin "38") (pinfunction "38_38") (pintype "bidirectional"))
    )
    (net (code "50") (name "PE0{slash}RX0") (class "Default")
      (node (ref "IC1") (pin "2") (pinfunction "(RXD0/PCIN8)PE0_2") (pintype "bidirectional"))
      (node (ref "R10") (pin "2") (pinfunction "2_2") (pintype "passive"))
      (node (ref "RX") (pin "C") (pinfunction "C_C") (pintype "passive"))
      (node (ref "U2") (pin "0") (pinfunction "0(RX0)_0") (pintype "bidirectional"))
    )
    (net (code "51") (name "PE1{slash}TX0") (class "Default")
      (node (ref "IC1") (pin "3") (pinfunction "(TXD0)PE1_3") (pintype "bidirectional"))
      (node (ref "R11") (pin "2") (pinfunction "2_2") (pintype "passive"))
      (node (ref "TX") (pin "C") (pinfunction "C_C") (pintype "passive"))
      (node (ref "U2") (pin "1") (pinfunction "1(TX0)_1") (pintype "bidirectional"))
    )
    (net (code "52") (name "PE2") (class "Default")
      (node (ref "IC1") (pin "4") (pinfunction "(XCK0/AIN0)PE2_4") (pintype "bidirectional"))
      (node (ref "X1") (pin "1") (pinfunction "1_1") (pintype "passive"))
    )
    (net (code "53") (name "PE3{slash}IO5~{}") (class "Default")
      (node (ref "IC1") (pin "5") (pinfunction "(OC3A/AIN1)PE3_5") (pintype "bidirectional"))
      (node (ref "U2") (pin "5") (pinfunction "5_5") (pintype "bidirectional"))
    )
    (net (code "54") (name "PE4{slash}IO2~{}") (class "Default")
      (node (ref "IC1") (pin "6") (pinfunction "(OC3B/INT4)PE4_6") (pintype "bidirectional"))
      (node (ref "U2") (pin "2") (pinfunction "2_2") (pintype "bidirectional"))
    )
    (net (code "55") (name "PE5{slash}IO3~{}") (class "Default")
      (node (ref "IC1") (pin "7") (pinfunction "(OC3C/INT5)PE5_7") (pintype "bidirectional"))
      (node (ref "U2") (pin "3") (pinfunction "3_3") (pintype "bidirectional"))
    )
    (net (code "56") (name "PE6") (class "Default")
      (node (ref "IC1") (pin "8") (pinfunction "(T3/INT6)PE6_8") (pintype "bidirectional"))
      (node (ref "X1") (pin "2") (pinfunction "2_2") (pintype "passive"))
    )
    (net (code "57") (name "PE7") (class "Default")
      (node (ref "IC1") (pin "9") (pinfunction "(CLKO/ICP3/INT7)PE7_9") (pintype "bidirectional"))
      (node (ref "X1") (pin "3") (pinfunction "3_3") (pintype "passive"))
    )
    (net (code "58") (name "PF0{slash}ADC0") (class "Default")
      (node (ref "IC1") (pin "97") (pinfunction "(ADC0)PF0_97") (pintype "bidirectional"))
      (node (ref "U2") (pin "A0") (pinfunction "A0(RX0)_A0") (pintype "bidirectional"))
    )
    (net (code "59") (name "PF1{slash}ADC1") (class "Default")
      (node (ref "IC1") (pin "96") (pinfunction "(ADC1)PF1_96") (pintype "bidirectional"))
      (node (ref "U2") (pin "A1") (pinfunction "A1(TX0)_A1") (pintype "bidirectional"))
    )
    (net (code "60") (name "PF2{slash}ADC2") (class "Default")
      (node (ref "IC1") (pin "95") (pinfunction "(ADC2)PF2_95") (pintype "bidirectional"))
      (node (ref "U2") (pin "A2") (pinfunction "A2_A2") (pintype "bidirectional"))
    )
    (net (code "61") (name "PF3{slash}ADC3") (class "Default")
      (node (ref "IC1") (pin "94") (pinfunction "(ADC3)PF3_94") (pintype "bidirectional"))
      (node (ref "U2") (pin "A3") (pinfunction "A3_A3") (pintype "bidirectional"))
    )
    (net (code "62") (name "PF4{slash}ADC4") (class "Default")
      (node (ref "IC1") (pin "93") (pinfunction "(ADC4/TCK)PF4_93") (pintype "bidirectional"))
      (node (ref "U2") (pin "A4") (pinfunction "A4_A4") (pintype "bidirectional"))
    )
    (net (code "63") (name "PF5{slash}ADC5") (class "Default")
      (node (ref "IC1") (pin "92") (pinfunction "(ADC5/TMS)PF5_92") (pintype "bidirectional"))
      (node (ref "U2") (pin "A5") (pinfunction "A5_A5") (pintype "bidirectional"))
    )
    (net (code "64") (name "PF6{slash}ADC6") (class "Default")
      (node (ref "IC1") (pin "91") (pinfunction "(ADC6/TDO)PF6_91") (pintype "bidirectional"))
      (node (ref "U2") (pin "A6") (pinfunction "A6_A6") (pintype "bidirectional"))
    )
    (net (code "65") (name "PF7{slash}ADC7") (class "Default")
      (node (ref "IC1") (pin "90") (pinfunction "(ADC7/TDI)PF7_90") (pintype "bidirectional"))
      (node (ref "U2") (pin "A7") (pinfunction "A7_A7") (pintype "bidirectional"))
    )
    (net (code "66") (name "PG0{slash}IO41") (class "Default")
      (node (ref "IC1") (pin "51") (pinfunction "(WR)PG0_51") (pintype "bidirectional"))
      (node (ref "U2") (pin "41") (pinfunction "41_41") (pintype "bidirectional"))
    )
    (net (code "67") (name "PG1{slash}IO40") (class "Default")
      (node (ref "IC1") (pin "52") (pinfunction "(RD)PG1_52") (pintype "bidirectional"))
      (node (ref "U2") (pin "40") (pinfunction "40_40") (pintype "bidirectional"))
    )
    (net (code "68") (name "PG2{slash}IO39") (class "Default")
      (node (ref "IC1") (pin "70") (pinfunction "(ALE)PG2_70") (pintype "bidirectional"))
      (node (ref "U2") (pin "39") (pinfunction "39_39") (pintype "bidirectional"))
    )
    (net (code "69") (name "PG3") (class "Default")
      (node (ref "IC1") (pin "28") (pinfunction "(TOSC2)PG3_28") (pintype "bidirectional"))
      (node (ref "X4") (pin "2") (pinfunction "2_2") (pintype "passive"))
    )
    (net (code "70") (name "PG4") (class "Default")
      (node (ref "IC1") (pin "29") (pinfunction "(TOSC1)PG4_29") (pintype "bidirectional"))
      (node (ref "X4") (pin "1") (pinfunction "1_1") (pintype "passive"))
    )
    (net (code "71") (name "PG5{slash}IO4~{}") (class "Default")
      (node (ref "IC1") (pin "1") (pinfunction "(OC0B)PG5_1") (pintype "bidirectional"))
      (node (ref "U2") (pin "4") (pinfunction "4_4") (pintype "bidirectional"))
    )
    (net (code "72") (name "PH0{slash}RXD2{slash}IO17") (class "Default")
      (node (ref "IC1") (pin "12") (pinfunction "PH0(RXD2)_12") (pintype "bidirectional"))
      (node (ref "U2") (pin "17") (pinfunction "17(RX2)_17") (pintype "bidirectional"))
    )
    (net (code "73") (name "PH1{slash}TXD2{slash}IO16") (class "Default")
      (node (ref "IC1") (pin "13") (pinfunction "PH1(TXD2)_13") (pintype "bidirectional"))
      (node (ref "U2") (pin "16") (pinfunction "16(TX2)_16") (pintype "bidirectional"))
    )
    (net (code "74") (name "PH2") (class "Default")
      (node (ref "IC1") (pin "14") (pinfunction "PH2(XCK2)_14") (pintype "bidirectional"))
      (node (ref "X1") (pin "4") (pinfunction "4_4") (pintype "passive"))
    )
    (net (code "75") (name "PH3{slash}IO6~{}") (class "Default")
      (node (ref "IC1") (pin "15") (pinfunction "PH3(OC4A)_15") (pintype "bidirectional"))
      (node (ref "U2") (pin "6") (pinfunction "6_6") (pintype "bidirectional"))
    )
    (net (code "76") (name "PH4{slash}IO7~{}") (class "Default")
      (node (ref "IC1") (pin "16") (pinfunction "PH4(OC4B)_16") (pintype "bidirectional"))
      (node (ref "U2") (pin "7") (pinfunction "7_7") (pintype "bidirectional"))
    )
    (net (code "77") (name "PH5{slash}IO8~{}") (class "Default")
      (node (ref "IC1") (pin "17") (pinfunction "PH5(OC4C)_17") (pintype "bidirectional"))
      (node (ref "U2") (pin "8") (pinfunction "8_8") (pintype "bidirectional"))
    )
    (net (code "78") (name "PH6{slash}IO9~{}") (class "Default")
      (node (ref "IC1") (pin "18") (pinfunction "PH6(OC2B)_18") (pintype "bidirectional"))
      (node (ref "U2") (pin "9") (pinfunction "9_9") (pintype "bidirectional"))
    )
    (net (code "79") (name "PH7") (class "Default")
      (node (ref "IC1") (pin "27") (pinfunction "PH7(T4)_27") (pintype "bidirectional"))
      (node (ref "X4") (pin "3") (pinfunction "3_3") (pintype "passive"))
    )
    (net (code "80") (name "PJ0{slash}RXD3{slash}IO15") (class "Default")
      (node (ref "IC1") (pin "63") (pinfunction "PJ0(RXD3/PCINT9)_63") (pintype "bidirectional"))
      (node (ref "U2") (pin "15") (pinfunction "15(RX3)_15") (pintype "bidirectional"))
    )
    (net (code "81") (name "PJ1{slash}TXD3{slash}IO14") (class "Default")
      (node (ref "IC1") (pin "64") (pinfunction "PJ1(TXD3/PCINT10)_64") (pintype "bidirectional"))
      (node (ref "U2") (pin "14") (pinfunction "14(TX3)_14") (pintype "bidirectional"))
    )
    (net (code "82") (name "PJ2") (class "Default")
      (node (ref "IC1") (pin "65") (pinfunction "PJ2(XCK3/PCINT11)_65") (pintype "bidirectional"))
      (node (ref "X3") (pin "6") (pinfunction "6_6") (pintype "passive"))
    )
    (net (code "83") (name "PJ3") (class "Default")
      (node (ref "IC1") (pin "66") (pinfunction "PJ3(PCINT12)_66") (pintype "bidirectional"))
      (node (ref "X3") (pin "5") (pinfunction "5_5") (pintype "passive"))
    )
    (net (code "84") (name "PJ4") (class "Default")
      (node (ref "IC1") (pin "67") (pinfunction "PJ4(PCINT13)_67") (pintype "bidirectional"))
      (node (ref "X3") (pin "4") (pinfunction "4_4") (pintype "passive"))
    )
    (net (code "85") (name "PJ5") (class "Default")
      (node (ref "IC1") (pin "68") (pinfunction "PJ5(PCINT14)_68") (pintype "bidirectional"))
      (node (ref "X3") (pin "3") (pinfunction "3_3") (pintype "passive"))
    )
    (net (code "86") (name "PJ6") (class "Default")
      (node (ref "IC1") (pin "69") (pinfunction "PJ6(PCINT15)_69") (pintype "bidirectional"))
      (node (ref "X3") (pin "2") (pinfunction "2_2") (pintype "passive"))
    )
    (net (code "87") (name "PJ7") (class "Default")
      (node (ref "IC1") (pin "79") (pinfunction "PJ7_79") (pintype "bidirectional"))
      (node (ref "X3") (pin "1") (pinfunction "1_1") (pintype "passive"))
    )
    (net (code "88") (name "PK0{slash}ADC8") (class "Default")
      (node (ref "IC1") (pin "89") (pinfunction "PK0(ADC8/PCINT16)_89") (pintype "bidirectional"))
      (node (ref "U2") (pin "A8") (pinfunction "A8_A8") (pintype "bidirectional"))
    )
    (net (code "89") (name "PK1{slash}ADC9") (class "Default")
      (node (ref "IC1") (pin "88") (pinfunction "PK1(ADC9/PCINT17)_88") (pintype "bidirectional"))
      (node (ref "U2") (pin "A9") (pinfunction "A9_A9") (pintype "bidirectional"))
    )
    (net (code "90") (name "PK2{slash}ADC10") (class "Default")
      (node (ref "IC1") (pin "87") (pinfunction "PK2(ADC10/PCINT18)_87") (pintype "bidirectional"))
      (node (ref "U2") (pin "A10") (pinfunction "A10_A10") (pintype "bidirectional"))
    )
    (net (code "91") (name "PK3{slash}ADC11") (class "Default")
      (node (ref "IC1") (pin "86") (pinfunction "PK3(ADC11/PCINT19)_86") (pintype "bidirectional"))
      (node (ref "U2") (pin "A11") (pinfunction "A11_A11") (pintype "bidirectional"))
    )
    (net (code "92") (name "PK4{slash}ADC12") (class "Default")
      (node (ref "IC1") (pin "85") (pinfunction "PK4(ADC12/PCINT20)_85") (pintype "bidirectional"))
      (node (ref "U2") (pin "A12") (pinfunction "A12_A12") (pintype "bidirectional"))
    )
    (net (code "93") (name "PK5{slash}ADC13") (class "Default")
      (node (ref "IC1") (pin "84") (pinfunction "PK5(ADC13/PCINT21)_84") (pintype "bidirectional"))
      (node (ref "U2") (pin "A13") (pinfunction "A13_A13") (pintype "bidirectional"))
    )
    (net (code "94") (name "PK6{slash}ADC14") (class "Default")
      (node (ref "IC1") (pin "83") (pinfunction "PK6(ADC14/PCINT22)_83") (pintype "bidirectional"))
      (node (ref "U2") (pin "A14") (pinfunction "A14_A14") (pintype "bidirectional"))
    )
    (net (code "95") (name "PK7{slash}ADC15") (class "Default")
      (node (ref "IC1") (pin "82") (pinfunction "PK7(ADC15/PCINT23)_82") (pintype "bidirectional"))
      (node (ref "U2") (pin "A15") (pinfunction "A15_A15") (pintype "bidirectional"))
    )
    (net (code "96") (name "PL0{slash}IO49") (class "Default")
      (node (ref "IC1") (pin "35") (pinfunction "PL0(ICP4)_35") (pintype "bidirectional"))
      (node (ref "U2") (pin "49") (pinfunction "49_49") (pintype "bidirectional"))
    )
    (net (code "97") (name "PL1{slash}IO48") (class "Default")
      (node (ref "IC1") (pin "36") (pinfunction "PL1(ICP5)_36") (pintype "bidirectional"))
      (node (ref "U2") (pin "48") (pinfunction "48_48") (pintype "bidirectional"))
    )
    (net (code "98") (name "PL2{slash}IO47") (class "Default")
      (node (ref "IC1") (pin "37") (pinfunction "PL2(T5)_37") (pintype "bidirectional"))
      (node (ref "U2") (pin "47") (pinfunction "47_47") (pintype "bidirectional"))
    )
    (net (code "99") (name "PL3{slash}IO46~{}") (class "Default")
      (node (ref "IC1") (pin "38") (pinfunction "PL3(OC5A)_38") (pintype "bidirectional"))
      (node (ref "U2") (pin "46") (pinfunction "46_46") (pintype "bidirectional"))
    )
    (net (code "100") (name "PL4{slash}IO45~{}") (class "Default")
      (node (ref "IC1") (pin "39") (pinfunction "PL4(OC5B)_39") (pintype "bidirectional"))
      (node (ref "U2") (pin "45") (pinfunction "45_45") (pintype "bidirectional"))
    )
    (net (code "101") (name "PL5{slash}IO44~{}") (class "Default")
      (node (ref "IC1") (pin "40") (pinfunction "PL5(OC5C)_40") (pintype "bidirectional"))
      (node (ref "U2") (pin "44") (pinfunction "44_44") (pintype "bidirectional"))
    )
    (net (code "102") (name "PL6{slash}IO43") (class "Default")
      (node (ref "IC1") (pin "41") (pinfunction "PL6_41") (pintype "bidirectional"))
      (node (ref "U2") (pin "43") (pinfunction "43_43") (pintype "bidirectional"))
    )
    (net (code "103") (name "PL7{slash}IO42") (class "Default")
      (node (ref "IC1") (pin "42") (pinfunction "PL7_42") (pintype "bidirectional"))
      (node (ref "U2") (pin "42") (pinfunction "42_42") (pintype "bidirectional"))
    )
    (net (code "104") (name "RESET") (class "Default")
      (node (ref "C1") (pin "1") (pinfunction "1_1") (pintype "passive"))
      (node (ref "IC1") (pin "30") (pinfunction "RESET_30") (pintype "input"))
      (node (ref "IC3") (pin "13") (pinfunction "DTR_13") (pintype "bidirectional"))
      (node (ref "ICSP") (pin "5") (pinfunction "5_5") (pintype "passive"))
      (node (ref "R3") (pin "1") (pinfunction "1_1") (pintype "passive"))
      (node (ref "RESET") (pin "1") (pinfunction "1_1") (pintype "passive"))
      (node (ref "U2") (pin "RESET") (pinfunction "RESET_RESET") (pintype "bidirectional"))
    )
    (net (code "105") (name "RI") (class "Default")
      (node (ref "IC3") (pin "11") (pinfunction "RI_11") (pintype "bidirectional"))
      (node (ref "J5") (pin "4") (pinfunction "4_4") (pintype "passive"))
    )
    (net (code "106") (name "USB_N") (class "Default")
      (node (ref "IC3") (pin "6") (pinfunction "D-_6") (pintype "bidirectional"))
      (node (ref "J6") (pin "D-") (pinfunction "D-_D-") (pintype "bidirectional"))
    )
    (net (code "107") (name "USB_P") (class "Default")
      (node (ref "IC3") (pin "5") (pinfunction "D+_5") (pintype "bidirectional"))
      (node (ref "J6") (pin "D+") (pinfunction "D+_D+") (pintype "bidirectional"))
    )
    (net (code "108") (name "VIN") (class "Default")
      (node (ref "C10") (pin "1") (pinfunction "1_1") (pintype "passive"))
      (node (ref "D1") (pin "C") (pinfunction "C_C") (pintype "passive"))
      (node (ref "IC4") (pin "3") (pinfunction "IN_3") (pintype "input"))
      (node (ref "J4") (pin "PWR") (pinfunction "PWR_PWR") (pintype "bidirectional"))
      (node (ref "U2") (pin "VIN") (pinfunction "VIN_VIN") (pintype "bidirectional"))
    )
    (net (code "109") (name "XTAL1") (class "Default")
      (node (ref "IC1") (pin "34") (pinfunction "XTAL1_34") (pintype "input"))
      (node (ref "R1") (pin "1") (pinfunction "1_1") (pintype "passive"))
      (node (ref "Y1") (pin "3") (pinfunction "3_3") (pintype "passive"))
    )
    (net (code "110") (name "XTAL2") (class "Default")
      (node (ref "IC1") (pin "33") (pinfunction "XTAL2_33") (pintype "output"))
      (node (ref "R1") (pin "2") (pinfunction "2_2") (pintype "passive"))
      (node (ref "Y1") (pin "1") (pinfunction "1_1") (pintype "passive"))
    )
    (net (code "111") (name "unconnected-(IC3-RS232-Pad15)") (class "Default")
      (node (ref "IC3") (pin "15") (pinfunction "RS232_15") (pintype "bidirectional"))
    )
    (net (code "112") (name "unconnected-(IC3-RTS-Pad14)") (class "Default")
      (node (ref "IC3") (pin "14") (pinfunction "RTS_14") (pintype "bidirectional"))
    )
  )
)
